# okinesio_v03.net
KiCad netlist of a schematic drawn in EAGLE
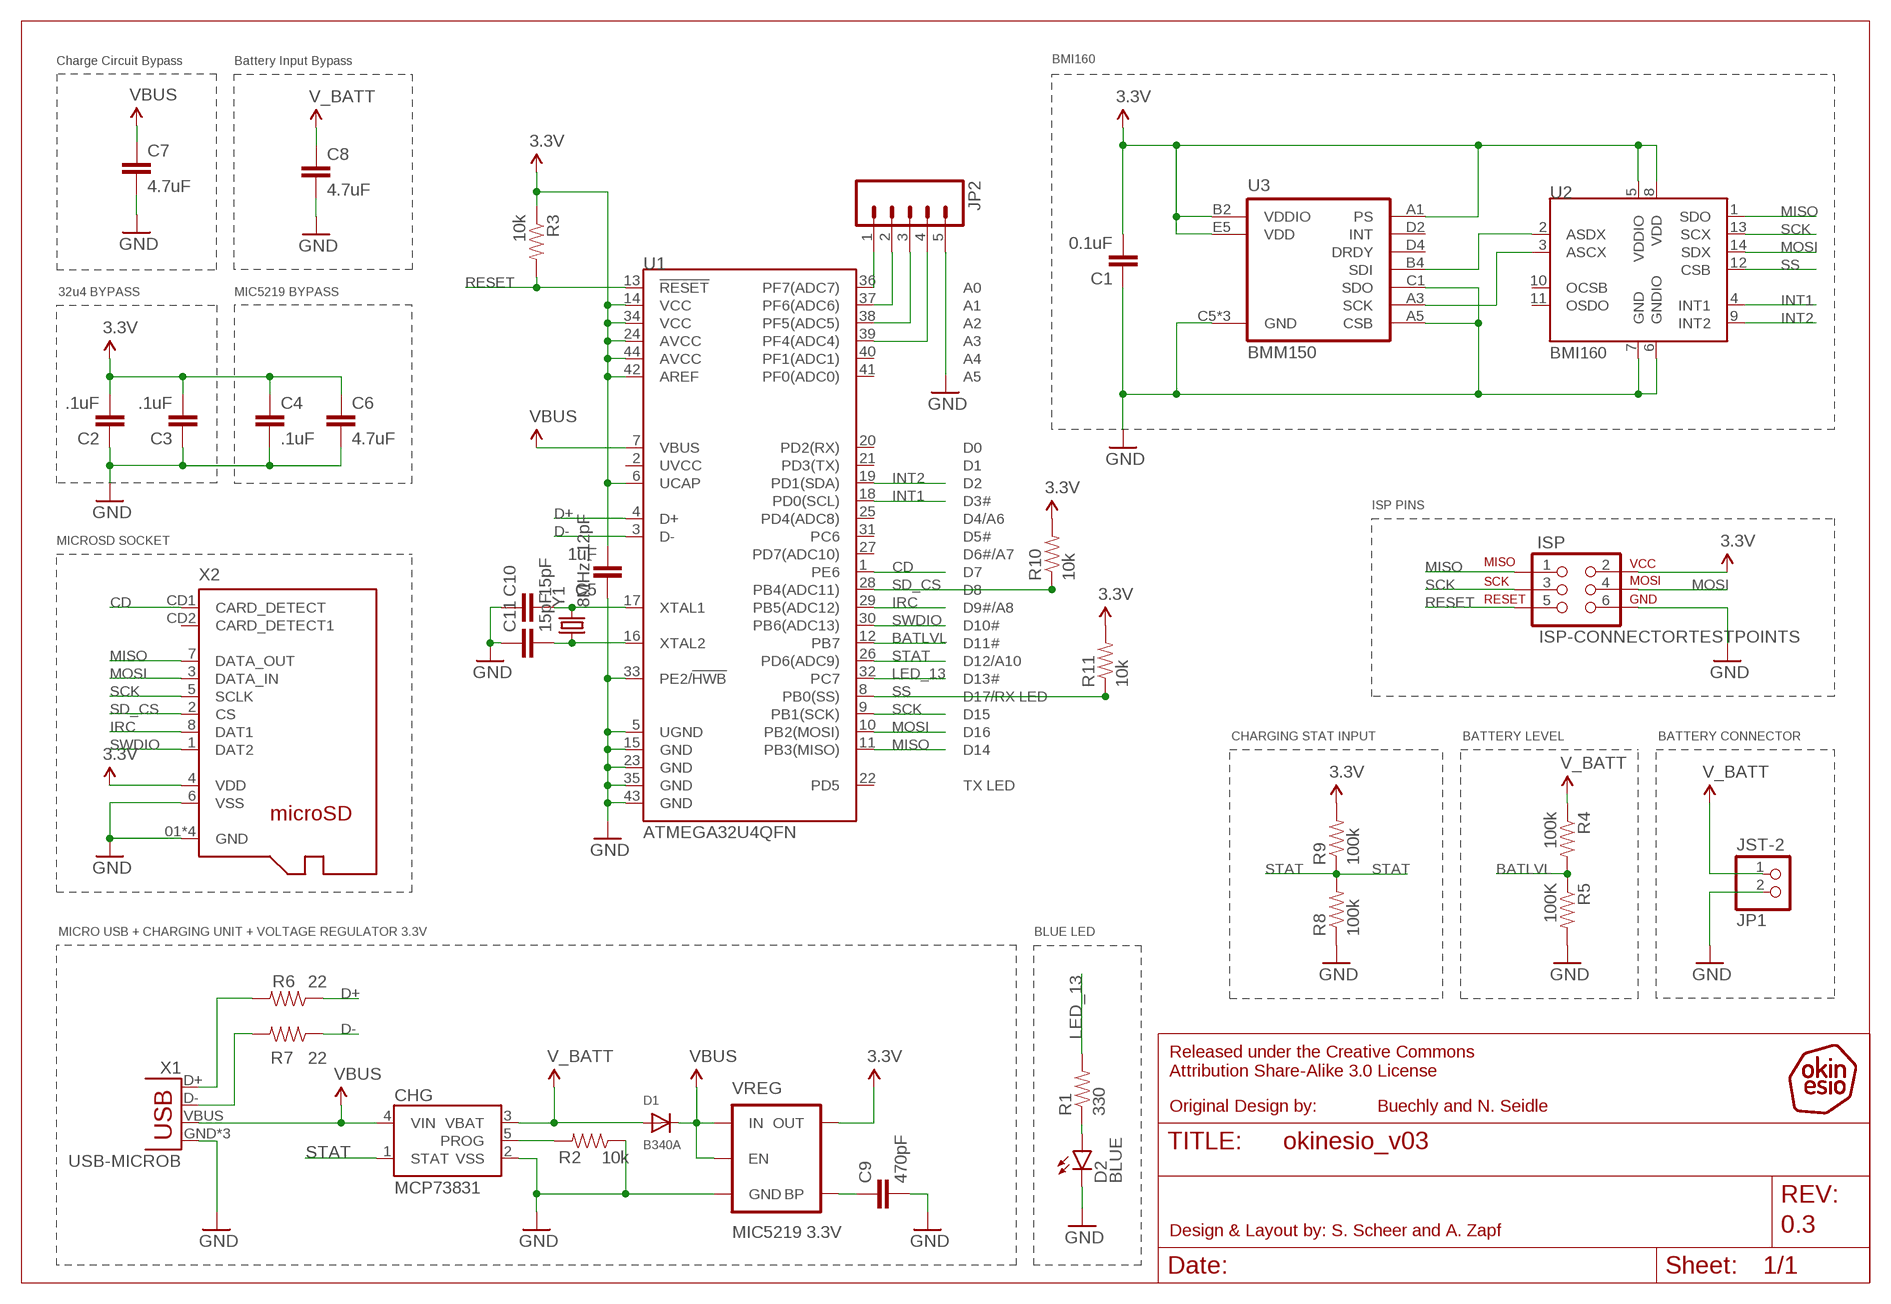
[diagram p0: schematic, sheet 1]

(export (version "E")
  (design (tool "Eeschema 10.0.6"))
  (components
    (comp (ref "C1")
      (value "0.1uF")
      (footprint "eagle-import:0603-CAP")
      (libsource (lib "eagle-import") (part "CAP0603-CAP"))
    )
    (comp (ref "C2")
      (value ".1uF")
      (footprint "eagle-import:0603-CAP")
      (libsource (lib "eagle-import") (part "SparkFun-Passives_CAP0603-CAP"))
    )
    (comp (ref "C3")
      (value ".1uF")
      (footprint "eagle-import:0603-CAP")
      (libsource (lib "eagle-import") (part "SparkFun-Passives_CAP0603-CAP"))
    )
    (comp (ref "C4")
      (value ".1uF")
      (footprint "eagle-import:0603-CAP")
      (libsource (lib "eagle-import") (part "CAP0603-CAP"))
    )
    (comp (ref "C5")
      (value "1uF")
      (footprint "eagle-import:0603-CAP")
      (libsource (lib "eagle-import") (part "SparkFun-Passives_CAP0603-CAP"))
    )
    (comp (ref "C6")
      (value "4.7uF")
      (footprint "eagle-import:0603-CAP")
      (libsource (lib "eagle-import") (part "CAP0603-CAP"))
    )
    (comp (ref "C7")
      (value "4.7uF")
      (footprint "eagle-import:0805")
      (libsource (lib "eagle-import") (part "CAP0805"))
    )
    (comp (ref "C8")
      (value "4.7uF")
      (footprint "eagle-import:0805")
      (libsource (lib "eagle-import") (part "CAP0805"))
    )
    (comp (ref "C9")
      (value "470pF")
      (footprint "eagle-import:0603-CAP")
      (libsource (lib "eagle-import") (part "SparkFun-Passives_CAP0603-CAP"))
    )
    (comp (ref "C10")
      (value "15pF")
      (footprint "eagle-import:0603-CAP")
      (libsource (lib "eagle-import") (part "CAP0603-CAP"))
    )
    (comp (ref "C11")
      (value "15pF")
      (footprint "eagle-import:0603-CAP")
      (libsource (lib "eagle-import") (part "CAP0603-CAP"))
    )
    (comp (ref "CHG")
      (value "MCP73831")
      (footprint "eagle-import:SOT23-5")
      (fields (field (name "PROD_ID") "IC-09995"))
      (libsource (lib "eagle-import") (part "MCP73831"))
    )
    (comp (ref "D1")
      (value "B340A")
      (footprint "eagle-import:SOD-123")
      (libsource (lib "eagle-import") (part "DIODESOD-123"))
    )
    (comp (ref "D2")
      (value "BLUE")
      (footprint "eagle-import:LED-0603")
      (libsource (lib "eagle-import") (part "LED-BLUE0603"))
    )
    (comp (ref "ISP")
      (value "ISP-CONNECTORTESTPOINTS")
      (footprint "eagle-import:2X3_TEST_POINTS")
      (libsource (lib "eagle-import") (part "ISP-CONNECTORTESTPOINTS"))
    )
    (comp (ref "JP1")
      (value "JST-2")
      (footprint "eagle-import:JST-PH-2-THM-RA")
      (libsource (lib "eagle-import") (part "JST_2PIN-THM-RA"))
    )
    (comp (ref "JP2")
      (value "M05PTH")
      (footprint "eagle-import:1X05")
      (libsource (lib "eagle-import") (part "M05PTH"))
    )
    (comp (ref "R1")
      (value "330")
      (footprint "eagle-import:0603-RES")
      (libsource (lib "eagle-import") (part "RESISTOR0603"))
    )
    (comp (ref "R2")
      (value "10k")
      (footprint "eagle-import:0603-RES")
      (libsource (lib "eagle-import") (part "RESISTOR0603-RES"))
    )
    (comp (ref "R3")
      (value "10k")
      (footprint "eagle-import:0603-RES")
      (libsource (lib "eagle-import") (part "RESISTOR0603-RES"))
    )
    (comp (ref "R4")
      (value "100k")
      (footprint "eagle-import:0603-RES")
      (libsource (lib "eagle-import") (part "RESISTOR0603-RES"))
    )
    (comp (ref "R5")
      (value "100K")
      (footprint "eagle-import:0603-RES")
      (libsource (lib "eagle-import") (part "RESISTOR0603-RES"))
    )
    (comp (ref "R6")
      (value "22")
      (footprint "eagle-import:0603-RES")
      (libsource (lib "eagle-import") (part "RESISTOR0603-RES"))
    )
    (comp (ref "R7")
      (value "22")
      (footprint "eagle-import:0603-RES")
      (libsource (lib "eagle-import") (part "RESISTOR0603-RES"))
    )
    (comp (ref "R8")
      (value "100k")
      (footprint "eagle-import:0603-RES")
      (libsource (lib "eagle-import") (part "RESISTOR0603-RES"))
    )
    (comp (ref "R9")
      (value "100k")
      (footprint "eagle-import:0603-RES")
      (libsource (lib "eagle-import") (part "RESISTOR0603-RES"))
    )
    (comp (ref "R10")
      (value "10k")
      (footprint "eagle-import:0603-RES")
      (libsource (lib "eagle-import") (part "RESISTOR0603-RES"))
    )
    (comp (ref "R11")
      (value "10k")
      (footprint "eagle-import:0603-RES")
      (libsource (lib "eagle-import") (part "RESISTOR0603-RES"))
    )
    (comp (ref "U$4")
      (value "OKINESIO-LOGO-2.85X2.81MM")
      (footprint "eagle-import:LOGO-STANDARD")
      (libsource (lib "eagle-import") (part "OKINESIO-LOGO-2.85X2.81MM"))
    )
    (comp (ref "U1")
      (value "ATMEGA32U4QFN")
      (footprint "eagle-import:QFN-44")
      (libsource (lib "eagle-import") (part "ATMEGA32U4QFN"))
    )
    (comp (ref "U2")
      (value "BMI160LGA14")
      (footprint "eagle-import:LGA14-BMI160")
      (libsource (lib "eagle-import") (part "BMI160LGA14"))
    )
    (comp (ref "U3")
      (value "BMM150")
      (footprint "eagle-import:WLCSP12-1.56X1.56")
      (libsource (lib "eagle-import") (part "BMM150"))
    )
    (comp (ref "VREG")
      (value "MIC5219 3.3V")
      (footprint "eagle-import:SOT23-5")
      (fields (field (name "PROD_ID") "VREG-09872"))
      (libsource (lib "eagle-import") (part "V_REG_MIC52193.3V"))
    )
    (comp (ref "X1")
      (value "USB-MICROB")
      (footprint "eagle-import:USB-MICROB")
      (fields (field (name "PROD_ID") "CONN-09505"))
      (libsource (lib "eagle-import") (part "USB-MICROB"))
    )
    (comp (ref "X2")
      (value "MICROSD-SOCKET")
      (footprint "eagle-import:MICROSD-SOCKET")
      (libsource (lib "eagle-import") (part "MICROSD-SOCKET"))
    )
    (comp (ref "Y1")
      (value "8MHz, 12pF")
      (footprint "eagle-import:CRYSTAL-TXC-7A")
      (libsource (lib "eagle-import") (part "CRYSTALTXC-7A"))
    )
  )
  (nets
    (net (code "1") (name "/BATLVL") (class "Default")
      (node (ref "R4") (pin "2") (pinfunction "2_2") (pintype "passive"))
      (node (ref "R5") (pin "1") (pinfunction "1_1") (pintype "passive"))
      (node (ref "U1") (pin "12") (pinfunction "PB7_12") (pintype "bidirectional"))
    )
    (net (code "2") (name "/CD") (class "Default")
      (node (ref "U1") (pin "1") (pinfunction "PE6_1") (pintype "bidirectional"))
      (node (ref "X2") (pin "CD1") (pinfunction "CARD_DETECT_CD1") (pintype "passive"))
    )
    (net (code "3") (name "/D+") (class "Default")
      (node (ref "R6") (pin "1") (pinfunction "1_1") (pintype "passive"))
      (node (ref "U1") (pin "4") (pinfunction "D+_4") (pintype "bidirectional"))
    )
    (net (code "4") (name "/D-") (class "Default")
      (node (ref "R7") (pin "1") (pinfunction "1_1") (pintype "passive"))
      (node (ref "U1") (pin "3") (pinfunction "D-_3") (pintype "bidirectional"))
    )
    (net (code "5") (name "/INT1") (class "Default")
      (node (ref "U1") (pin "18") (pinfunction "PD0(SCL)_18") (pintype "bidirectional"))
      (node (ref "U2") (pin "4") (pinfunction "INT1_4") (pintype "bidirectional"))
    )
    (net (code "6") (name "/INT2") (class "Default")
      (node (ref "U1") (pin "19") (pinfunction "PD1(SDA)_19") (pintype "bidirectional"))
      (node (ref "U2") (pin "9") (pinfunction "INT2_9") (pintype "bidirectional"))
    )
    (net (code "7") (name "/IRC") (class "Default")
      (node (ref "U1") (pin "29") (pinfunction "PB5(ADC12)_29") (pintype "bidirectional"))
      (node (ref "X2") (pin "8") (pinfunction "DAT1_8") (pintype "bidirectional"))
    )
    (net (code "8") (name "/LED_13") (class "Default")
      (node (ref "R1") (pin "2") (pinfunction "2_2") (pintype "passive"))
      (node (ref "U1") (pin "32") (pinfunction "PC7_32") (pintype "bidirectional"))
    )
    (net (code "9") (name "/MISO") (class "Default")
      (node (ref "ISP") (pin "1") (pinfunction "1_1") (pintype "passive"))
      (node (ref "U1") (pin "11") (pinfunction "PB3(MISO)_11") (pintype "bidirectional"))
      (node (ref "U2") (pin "1") (pinfunction "SDO_1") (pintype "bidirectional"))
      (node (ref "X2") (pin "7") (pinfunction "DATA_OUT_7") (pintype "output"))
    )
    (net (code "10") (name "/MOSI") (class "Default")
      (node (ref "ISP") (pin "4") (pinfunction "4_4") (pintype "passive"))
      (node (ref "U1") (pin "10") (pinfunction "PB2(MOSI)_10") (pintype "bidirectional"))
      (node (ref "U2") (pin "14") (pinfunction "SDX_14") (pintype "bidirectional"))
      (node (ref "X2") (pin "3") (pinfunction "DATA_IN_3") (pintype "input"))
    )
    (net (code "11") (name "/RESET") (class "Default")
      (node (ref "ISP") (pin "5") (pinfunction "5_5") (pintype "passive"))
      (node (ref "R3") (pin "2") (pinfunction "2_2") (pintype "passive"))
      (node (ref "U1") (pin "13") (pinfunction "~{RESET}_13") (pintype "bidirectional"))
    )
    (net (code "12") (name "/SCK") (class "Default")
      (node (ref "ISP") (pin "3") (pinfunction "3_3") (pintype "passive"))
      (node (ref "U1") (pin "9") (pinfunction "PB1(SCK)_9") (pintype "bidirectional"))
      (node (ref "U2") (pin "13") (pinfunction "SCX_13") (pintype "bidirectional"))
      (node (ref "X2") (pin "5") (pinfunction "SCLK_5") (pintype "input"))
    )
    (net (code "13") (name "/SD_CS") (class "Default")
      (node (ref "R10") (pin "1") (pinfunction "1_1") (pintype "passive"))
      (node (ref "U1") (pin "28") (pinfunction "PB4(ADC11)_28") (pintype "bidirectional"))
      (node (ref "X2") (pin "2") (pinfunction "CS_2") (pintype "input"))
    )
    (net (code "14") (name "/SS") (class "Default")
      (node (ref "R11") (pin "1") (pinfunction "1_1") (pintype "passive"))
      (node (ref "U1") (pin "8") (pinfunction "PB0(SS)_8") (pintype "bidirectional"))
      (node (ref "U2") (pin "12") (pinfunction "CSB_12") (pintype "bidirectional"))
    )
    (net (code "15") (name "/STAT") (class "Default")
      (node (ref "CHG") (pin "1") (pinfunction "STAT_1") (pintype "output"))
      (node (ref "R8") (pin "2") (pinfunction "2_2") (pintype "passive"))
      (node (ref "R9") (pin "1") (pinfunction "1_1") (pintype "passive"))
      (node (ref "U1") (pin "26") (pinfunction "PD6(ADC9)_26") (pintype "bidirectional"))
    )
    (net (code "16") (name "/SWDIO") (class "Default")
      (node (ref "U1") (pin "30") (pinfunction "PB6(ADC13)_30") (pintype "bidirectional"))
      (node (ref "X2") (pin "1") (pinfunction "DAT2_1") (pintype "bidirectional"))
    )
    (net (code "17") (name "3.3V") (class "Default")
      (node (ref "C1") (pin "2") (pinfunction "2_2") (pintype "passive"))
      (node (ref "C2") (pin "2") (pinfunction "2_2") (pintype "passive"))
      (node (ref "C3") (pin "2") (pinfunction "2_2") (pintype "passive"))
      (node (ref "C4") (pin "1") (pinfunction "1_1") (pintype "passive"))
      (node (ref "C5") (pin "2") (pinfunction "2_2") (pintype "passive"))
      (node (ref "C6") (pin "1") (pinfunction "1_1") (pintype "passive"))
      (node (ref "ISP") (pin "2") (pinfunction "2_2") (pintype "passive"))
      (node (ref "R10") (pin "2") (pinfunction "2_2") (pintype "passive"))
      (node (ref "R11") (pin "2") (pinfunction "2_2") (pintype "passive"))
      (node (ref "R3") (pin "1") (pinfunction "1_1") (pintype "passive"))
      (node (ref "R9") (pin "2") (pinfunction "2_2") (pintype "passive"))
      (node (ref "U1") (pin "14") (pinfunction "VCC_14") (pintype "bidirectional"))
      (node (ref "U1") (pin "24") (pinfunction "AVCC_24") (pintype "bidirectional"))
      (node (ref "U1") (pin "34") (pinfunction "VCC_34") (pintype "bidirectional"))
      (node (ref "U1") (pin "42") (pinfunction "AREF_42") (pintype "bidirectional"))
      (node (ref "U1") (pin "44") (pinfunction "AVCC_44") (pintype "bidirectional"))
      (node (ref "U1") (pin "6") (pinfunction "UCAP_6") (pintype "bidirectional"))
      (node (ref "U2") (pin "5") (pinfunction "VDDIO_5") (pintype "power_in"))
      (node (ref "U2") (pin "8") (pinfunction "VDD_8") (pintype "power_in"))
      (node (ref "U3") (pin "A1") (pinfunction "PS_A1") (pintype "bidirectional"))
      (node (ref "U3") (pin "B2") (pinfunction "VDDIO_B2") (pintype "power_in"))
      (node (ref "U3") (pin "E5") (pinfunction "VDD_E5") (pintype "power_in"))
      (node (ref "VREG") (pin "5") (pinfunction "OUT_5") (pintype "passive"))
      (node (ref "X2") (pin "4") (pinfunction "VDD_4") (pintype "power_in"))
    )
    (net (code "18") (name "GND") (class "Default")
      (node (ref "C1") (pin "1") (pinfunction "1_1") (pintype "passive"))
      (node (ref "C10") (pin "1") (pinfunction "1_1") (pintype "passive"))
      (node (ref "C11") (pin "1") (pinfunction "1_1") (pintype "passive"))
      (node (ref "C2") (pin "1") (pinfunction "1_1") (pintype "passive"))
      (node (ref "C3") (pin "1") (pinfunction "1_1") (pintype "passive"))
      (node (ref "C4") (pin "2") (pinfunction "2_2") (pintype "passive"))
      (node (ref "C5") (pin "1") (pinfunction "1_1") (pintype "passive"))
      (node (ref "C6") (pin "2") (pinfunction "2_2") (pintype "passive"))
      (node (ref "C7") (pin "2") (pinfunction "2_2") (pintype "passive"))
      (node (ref "C8") (pin "2") (pinfunction "2_2") (pintype "passive"))
      (node (ref "C9") (pin "2") (pinfunction "2_2") (pintype "passive"))
      (node (ref "CHG") (pin "2") (pinfunction "VSS_2") (pintype "power_in"))
      (node (ref "D2") (pin "C") (pinfunction "C_C") (pintype "passive"))
      (node (ref "ISP") (pin "6") (pinfunction "6_6") (pintype "passive"))
      (node (ref "JP1") (pin "2") (pinfunction "1_2") (pintype "passive"))
      (node (ref "JP2") (pin "5") (pinfunction "5_5") (pintype "passive"))
      (node (ref "R2") (pin "1") (pinfunction "1_1") (pintype "passive"))
      (node (ref "R5") (pin "2") (pinfunction "2_2") (pintype "passive"))
      (node (ref "R8") (pin "1") (pinfunction "1_1") (pintype "passive"))
      (node (ref "U1") (pin "15") (pinfunction "GND_15") (pintype "bidirectional"))
      (node (ref "U1") (pin "23") (pinfunction "GND_23") (pintype "bidirectional"))
      (node (ref "U1") (pin "33") (pinfunction "PE2/~{HWB}_33") (pintype "bidirectional"))
      (node (ref "U1") (pin "35") (pinfunction "GND_35") (pintype "bidirectional"))
      (node (ref "U1") (pin "43") (pinfunction "GND_43") (pintype "bidirectional"))
      (node (ref "U1") (pin "5") (pinfunction "UGND_5") (pintype "bidirectional"))
      (node (ref "U2") (pin "6") (pinfunction "GNDIO_6") (pintype "power_in"))
      (node (ref "U2") (pin "7") (pinfunction "GND_7") (pintype "power_in"))
      (node (ref "U3") (pin "A5") (pinfunction "CSB_A5") (pintype "input"))
      (node (ref "U3") (pin "C1") (pinfunction "SDO_C1") (pintype "bidirectional"))
      (node (ref "U3") (pin "C5") (pinfunction "GND_C5") (pintype "power_in"))
      (node (ref "U3") (pin "E1") (pinfunction "GND_E1") (pintype "power_in"))
      (node (ref "U3") (pin "E3") (pinfunction "GND_E3") (pintype "power_in"))
      (node (ref "VREG") (pin "2") (pinfunction "GND_2") (pintype "input"))
      (node (ref "X1") (pin "GND") (pinfunction "GND_GND") (pintype "bidirectional"))
      (node (ref "X1") (pin "MT1") (pinfunction "GND_MT1") (pintype "bidirectional"))
      (node (ref "X1") (pin "MT2") (pinfunction "GND_MT2") (pintype "bidirectional"))
      (node (ref "X2") (pin "01") (pinfunction "GND_01") (pintype "power_in"))
      (node (ref "X2") (pin "02") (pinfunction "GND_02") (pintype "power_in"))
      (node (ref "X2") (pin "03") (pinfunction "GND_03") (pintype "power_in"))
      (node (ref "X2") (pin "04") (pinfunction "GND_04") (pintype "power_in"))
      (node (ref "X2") (pin "6") (pinfunction "VSS_6") (pintype "power_in"))
    )
    (net (code "19") (name "Net-(CHG-PROG)") (class "Default")
      (node (ref "CHG") (pin "5") (pinfunction "PROG_5") (pintype "input"))
      (node (ref "R2") (pin "2") (pinfunction "2_2") (pintype "passive"))
    )
    (net (code "20") (name "Net-(D2-PadA)") (class "Default")
      (node (ref "D2") (pin "A") (pinfunction "A_A") (pintype "passive"))
      (node (ref "R1") (pin "1") (pinfunction "1_1") (pintype "passive"))
    )
    (net (code "21") (name "Net-(R6-Pad2)") (class "Default")
      (node (ref "R6") (pin "2") (pinfunction "2_2") (pintype "passive"))
      (node (ref "X1") (pin "D+") (pinfunction "D+_D+") (pintype "bidirectional"))
    )
    (net (code "22") (name "Net-(R7-Pad2)") (class "Default")
      (node (ref "R7") (pin "2") (pinfunction "2_2") (pintype "passive"))
      (node (ref "X1") (pin "D-") (pinfunction "D-_D-") (pintype "bidirectional"))
    )
    (net (code "23") (name "Net-(U1-PF4(ADC4))") (class "Default")
      (node (ref "JP2") (pin "4") (pinfunction "4_4") (pintype "passive"))
      (node (ref "U1") (pin "39") (pinfunction "PF4(ADC4)_39") (pintype "bidirectional"))
    )
    (net (code "24") (name "Net-(U1-PF5(ADC5))") (class "Default")
      (node (ref "JP2") (pin "3") (pinfunction "3_3") (pintype "passive"))
      (node (ref "U1") (pin "38") (pinfunction "PF5(ADC5)_38") (pintype "bidirectional"))
    )
    (net (code "25") (name "Net-(U1-PF6(ADC6))") (class "Default")
      (node (ref "JP2") (pin "2") (pinfunction "2_2") (pintype "passive"))
      (node (ref "U1") (pin "37") (pinfunction "PF6(ADC6)_37") (pintype "bidirectional"))
    )
    (net (code "26") (name "Net-(U1-PF7(ADC7))") (class "Default")
      (node (ref "JP2") (pin "1") (pinfunction "1_1") (pintype "passive"))
      (node (ref "U1") (pin "36") (pinfunction "PF7(ADC7)_36") (pintype "bidirectional"))
    )
    (net (code "27") (name "Net-(U1-XTAL1)") (class "Default")
      (node (ref "C10") (pin "2") (pinfunction "2_2") (pintype "passive"))
      (node (ref "U1") (pin "17") (pinfunction "XTAL1_17") (pintype "bidirectional"))
      (node (ref "Y1") (pin "P$2") (pinfunction "2_P$2") (pintype "passive"))
    )
    (net (code "28") (name "Net-(U1-XTAL2)") (class "Default")
      (node (ref "C11") (pin "2") (pinfunction "2_2") (pintype "passive"))
      (node (ref "U1") (pin "16") (pinfunction "XTAL2_16") (pintype "bidirectional"))
      (node (ref "Y1") (pin "P$1") (pinfunction "1_P$1") (pintype "passive"))
    )
    (net (code "29") (name "Net-(U2-ASCX)") (class "Default")
      (node (ref "U2") (pin "3") (pinfunction "ASCX_3") (pintype "bidirectional"))
      (node (ref "U3") (pin "A3") (pinfunction "SCK_A3") (pintype "input"))
    )
    (net (code "30") (name "Net-(U2-ASDX)") (class "Default")
      (node (ref "U2") (pin "2") (pinfunction "ASDX_2") (pintype "bidirectional"))
      (node (ref "U3") (pin "B4") (pinfunction "SDI_B4") (pintype "bidirectional"))
    )
    (net (code "31") (name "Net-(VREG-BP)") (class "Default")
      (node (ref "C9") (pin "1") (pinfunction "1_1") (pintype "passive"))
      (node (ref "VREG") (pin "4") (pinfunction "BP_4") (pintype "input"))
    )
    (net (code "32") (name "VBUS") (class "Default")
      (node (ref "C7") (pin "1") (pinfunction "1_1") (pintype "passive"))
      (node (ref "CHG") (pin "4") (pinfunction "VIN_4") (pintype "power_in"))
      (node (ref "D1") (pin "C") (pinfunction "C_C") (pintype "passive"))
      (node (ref "U1") (pin "7") (pinfunction "VBUS_7") (pintype "bidirectional"))
      (node (ref "VREG") (pin "1") (pinfunction "IN_1") (pintype "input"))
      (node (ref "VREG") (pin "3") (pinfunction "EN_3") (pintype "input"))
      (node (ref "X1") (pin "VBUS") (pinfunction "VBUS_VBUS") (pintype "bidirectional"))
    )
    (net (code "33") (name "V_BATT") (class "Default")
      (node (ref "C8") (pin "1") (pinfunction "1_1") (pintype "passive"))
      (node (ref "CHG") (pin "3") (pinfunction "VBAT_3") (pintype "power_in"))
      (node (ref "D1") (pin "A") (pinfunction "A_A") (pintype "passive"))
      (node (ref "JP1") (pin "1") (pinfunction "2_1") (pintype "passive"))
      (node (ref "R4") (pin "1") (pinfunction "1_1") (pintype "passive"))
    )
    (net (code "34") (name "unconnected-(U1-PC6-Pad31)") (class "Default")
      (node (ref "U1") (pin "31") (pinfunction "PC6_31") (pintype "bidirectional"))
    )
    (net (code "35") (name "unconnected-(U1-PD2(RX)-Pad20)") (class "Default")
      (node (ref "U1") (pin "20") (pinfunction "PD2(RX)_20") (pintype "bidirectional"))
    )
    (net (code "36") (name "unconnected-(U1-PD3(TX)-Pad21)") (class "Default")
      (node (ref "U1") (pin "21") (pinfunction "PD3(TX)_21") (pintype "bidirectional"))
    )
    (net (code "37") (name "unconnected-(U1-PD4(ADC8)-Pad25)") (class "Default")
      (node (ref "U1") (pin "25") (pinfunction "PD4(ADC8)_25") (pintype "bidirectional"))
    )
    (net (code "38") (name "unconnected-(U1-PD5-Pad22)") (class "Default")
      (node (ref "U1") (pin "22") (pinfunction "PD5_22") (pintype "bidirectional"))
    )
    (net (code "39") (name "unconnected-(U1-PD7(ADC10)-Pad27)") (class "Default")
      (node (ref "U1") (pin "27") (pinfunction "PD7(ADC10)_27") (pintype "bidirectional"))
    )
    (net (code "40") (name "unconnected-(U1-PF0(ADC0)-Pad41)") (class "Default")
      (node (ref "U1") (pin "41") (pinfunction "PF0(ADC0)_41") (pintype "bidirectional"))
    )
    (net (code "41") (name "unconnected-(U1-PF1(ADC1)-Pad40)") (class "Default")
      (node (ref "U1") (pin "40") (pinfunction "PF1(ADC1)_40") (pintype "bidirectional"))
    )
    (net (code "42") (name "unconnected-(U1-UVCC-Pad2)") (class "Default")
      (node (ref "U1") (pin "2") (pinfunction "UVCC_2") (pintype "bidirectional"))
    )
    (net (code "43") (name "unconnected-(U2-OCSB-Pad10)") (class "Default")
      (node (ref "U2") (pin "10") (pinfunction "OCSB_10") (pintype "bidirectional"))
    )
    (net (code "44") (name "unconnected-(U2-OSDO-Pad11)") (class "Default")
      (node (ref "U2") (pin "11") (pinfunction "OSDO_11") (pintype "bidirectional"))
    )
    (net (code "45") (name "unconnected-(U3-DRDY-PadD4)") (class "Default")
      (node (ref "U3") (pin "D4") (pinfunction "DRDY_D4") (pintype "bidirectional"))
    )
    (net (code "46") (name "unconnected-(U3-INT-PadD2)") (class "Default")
      (node (ref "U3") (pin "D2") (pinfunction "INT_D2") (pintype "output"))
    )
    (net (code "47") (name "unconnected-(X2-CARD_DETECT1-PadCD2)") (class "Default")
      (node (ref "X2") (pin "CD2") (pinfunction "CARD_DETECT1_CD2") (pintype "passive"))
    )
  )
)
